# Tiva_C_Base.net
KiCad netlist of a schematic drawn in Altium Designer
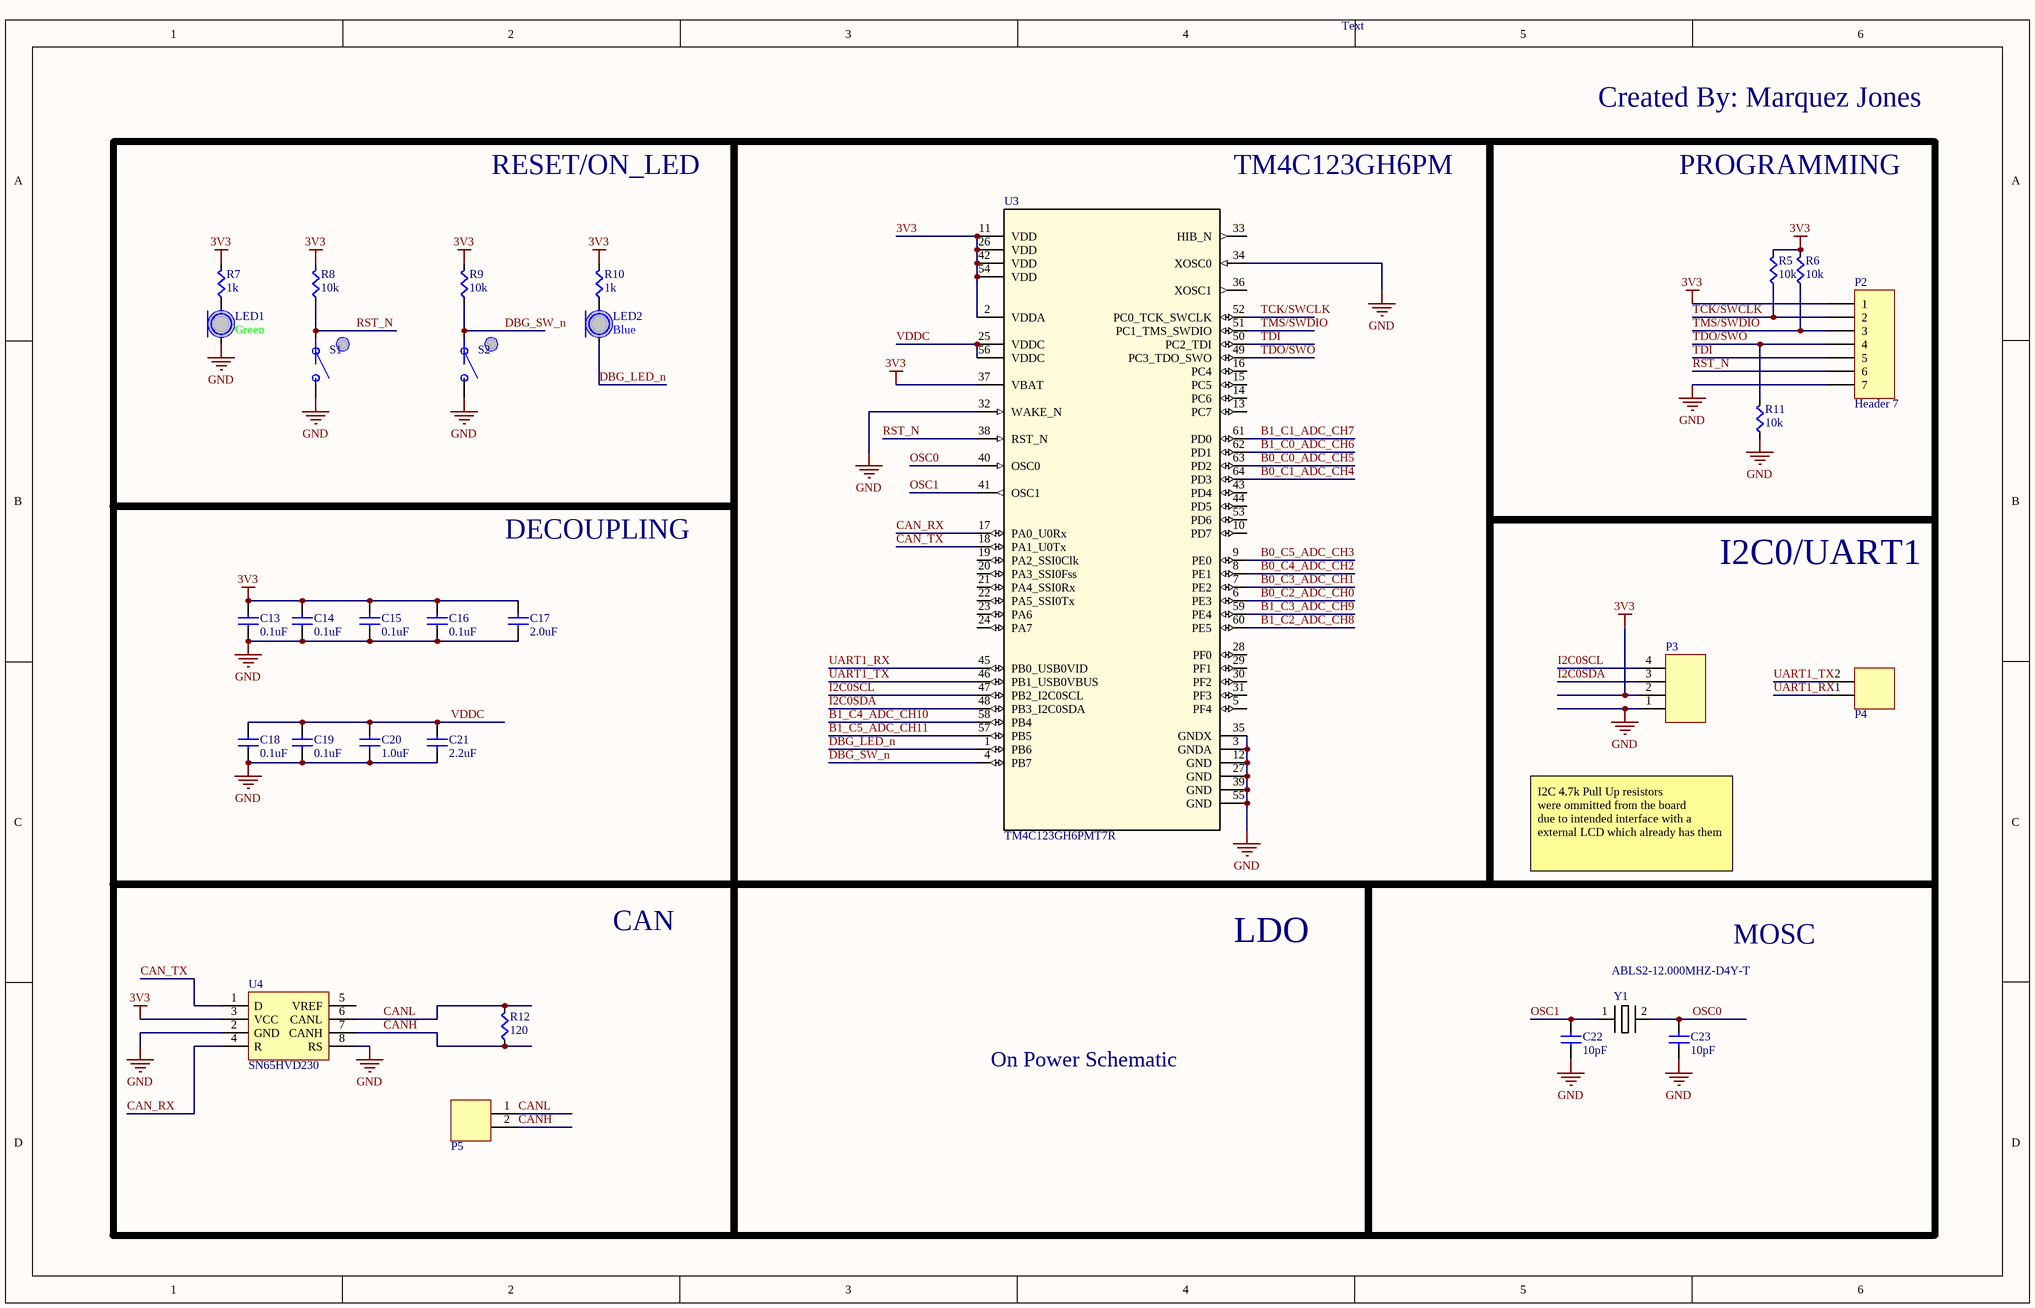
[diagram p0: Tiva_C_Base.SchDoc]

(export (version "E")
  (design (tool "Eeschema 10.0.6"))
  (components
    (comp (ref "C13")
      (value "0.1uF")
      (footprint "CAPC0603")
      (fields (field (name "Comment") "Cap"))
      (libsource (lib "SubjuGator8") (part "Cap"))
    )
    (comp (ref "C14")
      (value "0.1uF")
      (footprint "CAPC0603")
      (fields (field (name "Comment") "Cap"))
      (libsource (lib "SubjuGator8") (part "Cap"))
    )
    (comp (ref "C15")
      (value "0.1uF")
      (footprint "CAPC0603")
      (fields (field (name "Comment") "Cap"))
      (libsource (lib "SubjuGator8") (part "Cap"))
    )
    (comp (ref "C16")
      (value "0.1uF")
      (footprint "CAPC0603")
      (fields (field (name "Comment") "Cap"))
      (libsource (lib "SubjuGator8") (part "Cap"))
    )
    (comp (ref "C17")
      (value "2.0uF")
      (footprint "CAPC0603")
      (fields (field (name "Comment") "Cap"))
      (libsource (lib "SubjuGator8") (part "Cap"))
    )
    (comp (ref "C18")
      (value "0.1uF")
      (footprint "CAPC0603")
      (fields (field (name "Comment") "Cap"))
      (libsource (lib "SubjuGator8") (part "Cap"))
    )
    (comp (ref "C19")
      (value "0.1uF")
      (footprint "CAPC0603")
      (fields (field (name "Comment") "Cap"))
      (libsource (lib "SubjuGator8") (part "Cap"))
    )
    (comp (ref "C20")
      (value "1.0uF")
      (footprint "CAPC0603")
      (fields (field (name "Comment") "Cap"))
      (libsource (lib "SubjuGator8") (part "Cap"))
    )
    (comp (ref "C21")
      (value "2.2uF")
      (footprint "CAPC0603")
      (fields (field (name "Comment") "Cap"))
      (libsource (lib "SubjuGator8") (part "Cap"))
    )
    (comp (ref "C22")
      (value "10pF")
      (footprint "CAPC0603")
      (fields (field (name "Comment") "Cap"))
      (libsource (lib "Passives") (part "Cap"))
    )
    (comp (ref "C23")
      (value "10pF")
      (footprint "CAPC0603")
      (fields (field (name "Comment") "Cap"))
      (libsource (lib "Passives") (part "Cap"))
    )
    (comp (ref "LED1")
      (value "LED")
      (footprint "LED0603")
      (fields (field (name "COLOR") "Green"))
      (libsource (lib "SubjuGator8") (part "LED"))
    )
    (comp (ref "LED2")
      (value "LED")
      (footprint "LED0603")
      (fields (field (name "COLOR") "Blue"))
      (libsource (lib "SubjuGator8") (part "LED"))
    )
    (comp (ref "P2")
      (value "Header 7")
      (footprint "HDR1X7")
      (description "Header, 7-Pin")
      (fields (field (name "PUBLISHER") "Altium Limited"))
      (libsource (lib "Miscellaneous Connectors") (part "Header 7"))
    )
    (comp (ref "P3")
      (value "~")
      (footprint "MOLEX-HDR-1X4-SHERLOCK-VERT")
      (libsource (lib "SubjuGator8") (part "MOLEX-HDR-1x4-SHERLOCK_VERT"))
    )
    (comp (ref "P4")
      (value "2-pin Vert Sherlock")
      (footprint "MOLEX-HDR-1X2-SHERLOCK-VERT")
      (libsource (lib "") (part "MOLEX-HDR-1x2-SHERLOCK_VERT_1"))
    )
    (comp (ref "P5")
      (value "2-pin Vert Sherlock")
      (footprint "MOLEX-HDR-1X2-SHERLOCK-VERT")
      (libsource (lib "SubjuGator8") (part "MOLEX-HDR-1x2-SHERLOCK_VERT"))
    )
    (comp (ref "R5")
      (value "10k")
      (footprint "RES0603")
      (fields (field (name "Comment") "Res"))
      (libsource (lib "SubjuGator8") (part "Res"))
    )
    (comp (ref "R6")
      (value "10k")
      (footprint "RES0603")
      (fields (field (name "Comment") "Res"))
      (libsource (lib "SubjuGator8") (part "Res"))
    )
    (comp (ref "R7")
      (value "1k")
      (footprint "RES0603")
      (fields (field (name "Comment") "Res"))
      (libsource (lib "SubjuGator8") (part "Res"))
    )
    (comp (ref "R8")
      (value "10k")
      (footprint "RES0603")
      (fields (field (name "Comment") "Res"))
      (libsource (lib "SubjuGator8") (part "Res"))
    )
    (comp (ref "R9")
      (value "10k")
      (footprint "RES0603")
      (fields (field (name "Comment") "Res"))
      (libsource (lib "SubjuGator8") (part "Res"))
    )
    (comp (ref "R10")
      (value "1k")
      (footprint "RES0603")
      (fields (field (name "Comment") "Res"))
      (libsource (lib "SubjuGator8") (part "Res"))
    )
    (comp (ref "R11")
      (value "10k")
      (footprint "RES0603")
      (fields (field (name "Comment") "Res"))
      (libsource (lib "SubjuGator8") (part "Res"))
    )
    (comp (ref "R12")
      (value "120")
      (footprint "RES0603")
      (fields (field (name "Comment") "Res"))
      (libsource (lib "SubjuGator8") (part "Res"))
    )
    (comp (ref "S1")
      (value "Button")
      (footprint "PTS645xxxxSMTR92")
      (description "SPST Button")
      (libsource (lib "SubjuGator8") (part "Button"))
    )
    (comp (ref "S2")
      (value "Button")
      (footprint "PTS645xxxxSMTR92")
      (description "SPST Button")
      (libsource (lib "SubjuGator8") (part "Button"))
    )
    (comp (ref "U3")
      (value "TM4C123GH6PMT7R")
      (footprint "TM4C123GH6PMT7R_L")
      (description "Imported")
      (fields
        (field (name "PARTNUMBER") "TM4C123GH6PMTR")
        (field (name "ALTERNATE_PARTNUMBER") "TM4C123GH6PMT")
      )
      (libsource (lib "SubjuGator8") (part "TM4C123GH6PMT7R"))
    )
    (comp (ref "U4")
      (value "SN65HVD230")
      (footprint "SOIC-8pin")
      (description "3.3V CAN Bus Transceiver")
      (libsource (lib "SubjuGator8") (part "SN65HVD230"))
    )
    (comp (ref "Y1")
      (value "ABLS2-12.000MHZ-D4Y-T")
      (footprint "HC49/US")
      (description "12MHz ±30ppm Crystal 18pF 50 Ohm -40°C ~ 85°C Surface Mount HC49/US")
      (libsource (lib "SubjuGator8") (part "ABLS2-12.000MHZ-D4Y-T"))
    )
  )
  (nets
    (net (code "1") (name "/B0_C0_ADC_CH5") (class "Default")
      (node (ref "U3") (pin "63") (pinfunction "PD2_63") (pintype "bidirectional"))
    )
    (net (code "2") (name "/B0_C1_ADC_CH4") (class "Default")
      (node (ref "U3") (pin "64") (pinfunction "PD3_64") (pintype "bidirectional"))
    )
    (net (code "3") (name "/B0_C2_ADC_CH0") (class "Default")
      (node (ref "U3") (pin "6") (pinfunction "PE3_6") (pintype "bidirectional"))
    )
    (net (code "4") (name "/B0_C3_ADC_CH1") (class "Default")
      (node (ref "U3") (pin "7") (pinfunction "PE2_7") (pintype "bidirectional"))
    )
    (net (code "5") (name "/B0_C4_ADC_CH2") (class "Default")
      (node (ref "U3") (pin "8") (pinfunction "PE1_8") (pintype "bidirectional"))
    )
    (net (code "6") (name "/B0_C5_ADC_CH3") (class "Default")
      (node (ref "U3") (pin "9") (pinfunction "PE0_9") (pintype "bidirectional"))
    )
    (net (code "7") (name "/B1_C0_ADC_CH6") (class "Default")
      (node (ref "U3") (pin "62") (pinfunction "PD1_62") (pintype "bidirectional"))
    )
    (net (code "8") (name "/B1_C1_ADC_CH7") (class "Default")
      (node (ref "U3") (pin "61") (pinfunction "PD0_61") (pintype "bidirectional"))
    )
    (net (code "9") (name "/B1_C2_ADC_CH8") (class "Default")
      (node (ref "U3") (pin "60") (pinfunction "PE5_60") (pintype "bidirectional"))
    )
    (net (code "10") (name "/B1_C3_ADC_CH9") (class "Default")
      (node (ref "U3") (pin "59") (pinfunction "PE4_59") (pintype "bidirectional"))
    )
    (net (code "11") (name "/B1_C4_ADC_CH10") (class "Default")
      (node (ref "U3") (pin "58") (pinfunction "PB4_58") (pintype "bidirectional"))
    )
    (net (code "12") (name "/B1_C5_ADC_CH11") (class "Default")
      (node (ref "U3") (pin "57") (pinfunction "PB5_57") (pintype "bidirectional"))
    )
    (net (code "13") (name "/CANH") (class "Default")
      (node (ref "P5") (pin "2") (pinfunction "2_2") (pintype "passive"))
      (node (ref "R12") (pin "2") (pinfunction "B_2") (pintype "passive"))
      (node (ref "U4") (pin "7") (pinfunction "CANH_7") (pintype "passive"))
    )
    (net (code "14") (name "/CANL") (class "Default")
      (node (ref "P5") (pin "1") (pinfunction "1_1") (pintype "passive"))
      (node (ref "R12") (pin "1") (pinfunction "A_1") (pintype "passive"))
      (node (ref "U4") (pin "6") (pinfunction "CANL_6") (pintype "passive"))
    )
    (net (code "15") (name "/CAN_RX") (class "Default")
      (node (ref "U3") (pin "17") (pinfunction "PA0_U0Rx_17") (pintype "bidirectional"))
      (node (ref "U4") (pin "4") (pinfunction "R_4") (pintype "passive"))
    )
    (net (code "16") (name "/CAN_TX") (class "Default")
      (node (ref "U3") (pin "18") (pinfunction "PA1_U0Tx_18") (pintype "bidirectional"))
      (node (ref "U4") (pin "1") (pinfunction "D_1") (pintype "passive"))
    )
    (net (code "17") (name "/DBG_LED_n") (class "Default")
      (node (ref "LED2") (pin "C") (pinfunction "C_C") (pintype "passive"))
      (node (ref "U3") (pin "1") (pinfunction "PB6_1") (pintype "bidirectional"))
    )
    (net (code "18") (name "/DBG_SW_n") (class "Default")
      (node (ref "R9") (pin "2") (pinfunction "B_2") (pintype "passive"))
      (node (ref "S2") (pin "A") (pinfunction "A_A") (pintype "passive"))
      (node (ref "U3") (pin "4") (pinfunction "PB7_4") (pintype "bidirectional"))
    )
    (net (code "19") (name "/I2C0SCL") (class "Default")
      (node (ref "P3") (pin "4") (pinfunction "4_4") (pintype "passive"))
      (node (ref "U3") (pin "47") (pinfunction "PB2_I2C0SCL_47") (pintype "bidirectional"))
    )
    (net (code "20") (name "/I2C0SDA") (class "Default")
      (node (ref "P3") (pin "3") (pinfunction "3_3") (pintype "passive"))
      (node (ref "U3") (pin "48") (pinfunction "PB3_I2C0SDA_48") (pintype "bidirectional"))
    )
    (net (code "21") (name "/OSC0") (class "Default")
      (node (ref "C23") (pin "1") (pinfunction "A_1") (pintype "passive"))
      (node (ref "U3") (pin "40") (pinfunction "OSC0_40") (pintype "input"))
      (node (ref "Y1") (pin "2") (pinfunction "2_2") (pintype "passive"))
    )
    (net (code "22") (name "/OSC1") (class "Default")
      (node (ref "C22") (pin "1") (pinfunction "A_1") (pintype "passive"))
      (node (ref "U3") (pin "41") (pinfunction "OSC1_41") (pintype "output"))
      (node (ref "Y1") (pin "1") (pinfunction "1_1") (pintype "passive"))
    )
    (net (code "23") (name "/RST_N") (class "Default")
      (node (ref "P2") (pin "6") (pinfunction "6_6") (pintype "passive"))
      (node (ref "R8") (pin "2") (pinfunction "B_2") (pintype "passive"))
      (node (ref "S1") (pin "A") (pinfunction "A_A") (pintype "passive"))
      (node (ref "U3") (pin "38") (pinfunction "RST_N_38") (pintype "input"))
    )
    (net (code "24") (name "/TCK{slash}SWCLK") (class "Default")
      (node (ref "P2") (pin "2") (pinfunction "2_2") (pintype "passive"))
      (node (ref "R5") (pin "2") (pinfunction "B_2") (pintype "passive"))
      (node (ref "U3") (pin "52") (pinfunction "PC0_TCK_SWCLK_52") (pintype "bidirectional"))
    )
    (net (code "25") (name "/TDI") (class "Default")
      (node (ref "P2") (pin "5") (pinfunction "5_5") (pintype "passive"))
      (node (ref "U3") (pin "50") (pinfunction "PC2_TDI_50") (pintype "bidirectional"))
    )
    (net (code "26") (name "/TDO{slash}SWO") (class "Default")
      (node (ref "P2") (pin "4") (pinfunction "4_4") (pintype "passive"))
      (node (ref "R11") (pin "1") (pinfunction "A_1") (pintype "passive"))
      (node (ref "U3") (pin "49") (pinfunction "PC3_TDO_SWO_49") (pintype "bidirectional"))
    )
    (net (code "27") (name "/TMS{slash}SWDIO") (class "Default")
      (node (ref "P2") (pin "3") (pinfunction "3_3") (pintype "passive"))
      (node (ref "R6") (pin "2") (pinfunction "B_2") (pintype "passive"))
      (node (ref "U3") (pin "51") (pinfunction "PC1_TMS_SWDIO_51") (pintype "bidirectional"))
    )
    (net (code "28") (name "/UART1_RX") (class "Default")
      (node (ref "P4") (pin "1") (pinfunction "1_1") (pintype "passive"))
      (node (ref "U3") (pin "45") (pinfunction "PB0_USB0VID_45") (pintype "bidirectional"))
    )
    (net (code "29") (name "/UART1_TX") (class "Default")
      (node (ref "P4") (pin "2") (pinfunction "2_2") (pintype "passive"))
      (node (ref "U3") (pin "46") (pinfunction "PB1_USB0VBUS_46") (pintype "bidirectional"))
    )
    (net (code "30") (name "/VDDC") (class "Default")
      (node (ref "C18") (pin "1") (pinfunction "A_1") (pintype "passive"))
      (node (ref "C19") (pin "1") (pinfunction "A_1") (pintype "passive"))
      (node (ref "C20") (pin "1") (pinfunction "A_1") (pintype "passive"))
      (node (ref "C21") (pin "1") (pinfunction "A_1") (pintype "passive"))
      (node (ref "U3") (pin "25") (pinfunction "VDDC_25") (pintype "power_in"))
      (node (ref "U3") (pin "56") (pinfunction "VDDC_56") (pintype "power_in"))
    )
    (net (code "31") (name "3V3") (class "Default")
      (node (ref "C13") (pin "1") (pinfunction "A_1") (pintype "passive"))
      (node (ref "C14") (pin "1") (pinfunction "A_1") (pintype "passive"))
      (node (ref "C15") (pin "1") (pinfunction "A_1") (pintype "passive"))
      (node (ref "C16") (pin "1") (pinfunction "A_1") (pintype "passive"))
      (node (ref "C17") (pin "1") (pinfunction "A_1") (pintype "passive"))
      (node (ref "P2") (pin "1") (pinfunction "1_1") (pintype "passive"))
      (node (ref "P3") (pin "2") (pinfunction "2_2") (pintype "passive"))
      (node (ref "R10") (pin "1") (pinfunction "A_1") (pintype "passive"))
      (node (ref "R5") (pin "1") (pinfunction "A_1") (pintype "passive"))
      (node (ref "R6") (pin "1") (pinfunction "A_1") (pintype "passive"))
      (node (ref "R7") (pin "1") (pinfunction "A_1") (pintype "passive"))
      (node (ref "R8") (pin "1") (pinfunction "A_1") (pintype "passive"))
      (node (ref "R9") (pin "1") (pinfunction "A_1") (pintype "passive"))
      (node (ref "U3") (pin "11") (pinfunction "VDD_11") (pintype "power_in"))
      (node (ref "U3") (pin "2") (pinfunction "VDDA_2") (pintype "power_in"))
      (node (ref "U3") (pin "26") (pinfunction "VDD_26") (pintype "power_in"))
      (node (ref "U3") (pin "37") (pinfunction "VBAT_37") (pintype "power_in"))
      (node (ref "U3") (pin "42") (pinfunction "VDD_42") (pintype "power_in"))
      (node (ref "U3") (pin "54") (pinfunction "VDD_54") (pintype "power_in"))
      (node (ref "U4") (pin "3") (pinfunction "VCC_3") (pintype "passive"))
    )
    (net (code "32") (name "GND") (class "Default")
      (node (ref "C13") (pin "2") (pinfunction "B_2") (pintype "passive"))
      (node (ref "C14") (pin "2") (pinfunction "B_2") (pintype "passive"))
      (node (ref "C15") (pin "2") (pinfunction "B_2") (pintype "passive"))
      (node (ref "C16") (pin "2") (pinfunction "B_2") (pintype "passive"))
      (node (ref "C17") (pin "2") (pinfunction "B_2") (pintype "passive"))
      (node (ref "C18") (pin "2") (pinfunction "B_2") (pintype "passive"))
      (node (ref "C19") (pin "2") (pinfunction "B_2") (pintype "passive"))
      (node (ref "C20") (pin "2") (pinfunction "B_2") (pintype "passive"))
      (node (ref "C21") (pin "2") (pinfunction "B_2") (pintype "passive"))
      (node (ref "C22") (pin "2") (pinfunction "B_2") (pintype "passive"))
      (node (ref "C23") (pin "2") (pinfunction "B_2") (pintype "passive"))
      (node (ref "LED1") (pin "C") (pinfunction "C_C") (pintype "passive"))
      (node (ref "P2") (pin "7") (pinfunction "7_7") (pintype "passive"))
      (node (ref "P3") (pin "1") (pinfunction "1_1") (pintype "passive"))
      (node (ref "R11") (pin "2") (pinfunction "B_2") (pintype "passive"))
      (node (ref "S1") (pin "B") (pinfunction "B_B") (pintype "passive"))
      (node (ref "S2") (pin "B") (pinfunction "B_B") (pintype "passive"))
      (node (ref "U3") (pin "12") (pinfunction "GND_12") (pintype "power_in"))
      (node (ref "U3") (pin "27") (pinfunction "GND_27") (pintype "power_in"))
      (node (ref "U3") (pin "3") (pinfunction "GNDA_3") (pintype "power_in"))
      (node (ref "U3") (pin "32") (pinfunction "WAKE_N_32") (pintype "input"))
      (node (ref "U3") (pin "34") (pinfunction "XOSC0_34") (pintype "input"))
      (node (ref "U3") (pin "35") (pinfunction "GNDX_35") (pintype "power_in"))
      (node (ref "U3") (pin "39") (pinfunction "GND_39") (pintype "power_in"))
      (node (ref "U3") (pin "55") (pinfunction "GND_55") (pintype "power_in"))
      (node (ref "U4") (pin "2") (pinfunction "GND_2") (pintype "passive"))
      (node (ref "U4") (pin "8") (pinfunction "RS_8") (pintype "passive"))
    )
    (net (code "33") (name "Net-(R7-B)") (class "Default")
      (node (ref "LED1") (pin "A") (pinfunction "A_A") (pintype "passive"))
      (node (ref "R7") (pin "2") (pinfunction "B_2") (pintype "passive"))
    )
    (net (code "34") (name "Net-(R10-B)") (class "Default")
      (node (ref "LED2") (pin "A") (pinfunction "A_A") (pintype "passive"))
      (node (ref "R10") (pin "2") (pinfunction "B_2") (pintype "passive"))
    )
    (net (code "35") (name "unconnected-(U3-HIB_N-Pad33)") (class "Default")
      (node (ref "U3") (pin "33") (pinfunction "HIB_N_33") (pintype "output"))
    )
    (net (code "36") (name "unconnected-(U3-PA2_SSI0Clk-Pad19)") (class "Default")
      (node (ref "U3") (pin "19") (pinfunction "PA2_SSI0Clk_19") (pintype "bidirectional"))
    )
    (net (code "37") (name "unconnected-(U3-PA3_SSI0Fss-Pad20)") (class "Default")
      (node (ref "U3") (pin "20") (pinfunction "PA3_SSI0Fss_20") (pintype "bidirectional"))
    )
    (net (code "38") (name "unconnected-(U3-PA4_SSI0Rx-Pad21)") (class "Default")
      (node (ref "U3") (pin "21") (pinfunction "PA4_SSI0Rx_21") (pintype "bidirectional"))
    )
    (net (code "39") (name "unconnected-(U3-PA5_SSI0Tx-Pad22)") (class "Default")
      (node (ref "U3") (pin "22") (pinfunction "PA5_SSI0Tx_22") (pintype "bidirectional"))
    )
    (net (code "40") (name "unconnected-(U3-PA6-Pad23)") (class "Default")
      (node (ref "U3") (pin "23") (pinfunction "PA6_23") (pintype "bidirectional"))
    )
    (net (code "41") (name "unconnected-(U3-PA7-Pad24)") (class "Default")
      (node (ref "U3") (pin "24") (pinfunction "PA7_24") (pintype "bidirectional"))
    )
    (net (code "42") (name "unconnected-(U3-PC4-Pad16)") (class "Default")
      (node (ref "U3") (pin "16") (pinfunction "PC4_16") (pintype "bidirectional"))
    )
    (net (code "43") (name "unconnected-(U3-PC5-Pad15)") (class "Default")
      (node (ref "U3") (pin "15") (pinfunction "PC5_15") (pintype "bidirectional"))
    )
    (net (code "44") (name "unconnected-(U3-PC6-Pad14)") (class "Default")
      (node (ref "U3") (pin "14") (pinfunction "PC6_14") (pintype "bidirectional"))
    )
    (net (code "45") (name "unconnected-(U3-PC7-Pad13)") (class "Default")
      (node (ref "U3") (pin "13") (pinfunction "PC7_13") (pintype "bidirectional"))
    )
    (net (code "46") (name "unconnected-(U3-PD4-Pad43)") (class "Default")
      (node (ref "U3") (pin "43") (pinfunction "PD4_43") (pintype "bidirectional"))
    )
    (net (code "47") (name "unconnected-(U3-PD5-Pad44)") (class "Default")
      (node (ref "U3") (pin "44") (pinfunction "PD5_44") (pintype "bidirectional"))
    )
    (net (code "48") (name "unconnected-(U3-PD6-Pad53)") (class "Default")
      (node (ref "U3") (pin "53") (pinfunction "PD6_53") (pintype "bidirectional"))
    )
    (net (code "49") (name "unconnected-(U3-PD7-Pad10)") (class "Default")
      (node (ref "U3") (pin "10") (pinfunction "PD7_10") (pintype "bidirectional"))
    )
    (net (code "50") (name "unconnected-(U3-PF0-Pad28)") (class "Default")
      (node (ref "U3") (pin "28") (pinfunction "PF0_28") (pintype "bidirectional"))
    )
    (net (code "51") (name "unconnected-(U3-PF1-Pad29)") (class "Default")
      (node (ref "U3") (pin "29") (pinfunction "PF1_29") (pintype "bidirectional"))
    )
    (net (code "52") (name "unconnected-(U3-PF2-Pad30)") (class "Default")
      (node (ref "U3") (pin "30") (pinfunction "PF2_30") (pintype "bidirectional"))
    )
    (net (code "53") (name "unconnected-(U3-PF3-Pad31)") (class "Default")
      (node (ref "U3") (pin "31") (pinfunction "PF3_31") (pintype "bidirectional"))
    )
    (net (code "54") (name "unconnected-(U3-PF4-Pad5)") (class "Default")
      (node (ref "U3") (pin "5") (pinfunction "PF4_5") (pintype "bidirectional"))
    )
    (net (code "55") (name "unconnected-(U3-XOSC1-Pad36)") (class "Default")
      (node (ref "U3") (pin "36") (pinfunction "XOSC1_36") (pintype "output"))
    )
    (net (code "56") (name "unconnected-(U4-VREF-Pad5)") (class "Default")
      (node (ref "U4") (pin "5") (pinfunction "VREF_5") (pintype "passive"))
    )
  )
)
